# Processing-Section.net
KiCad netlist of a schematic drawn in Altium Designer
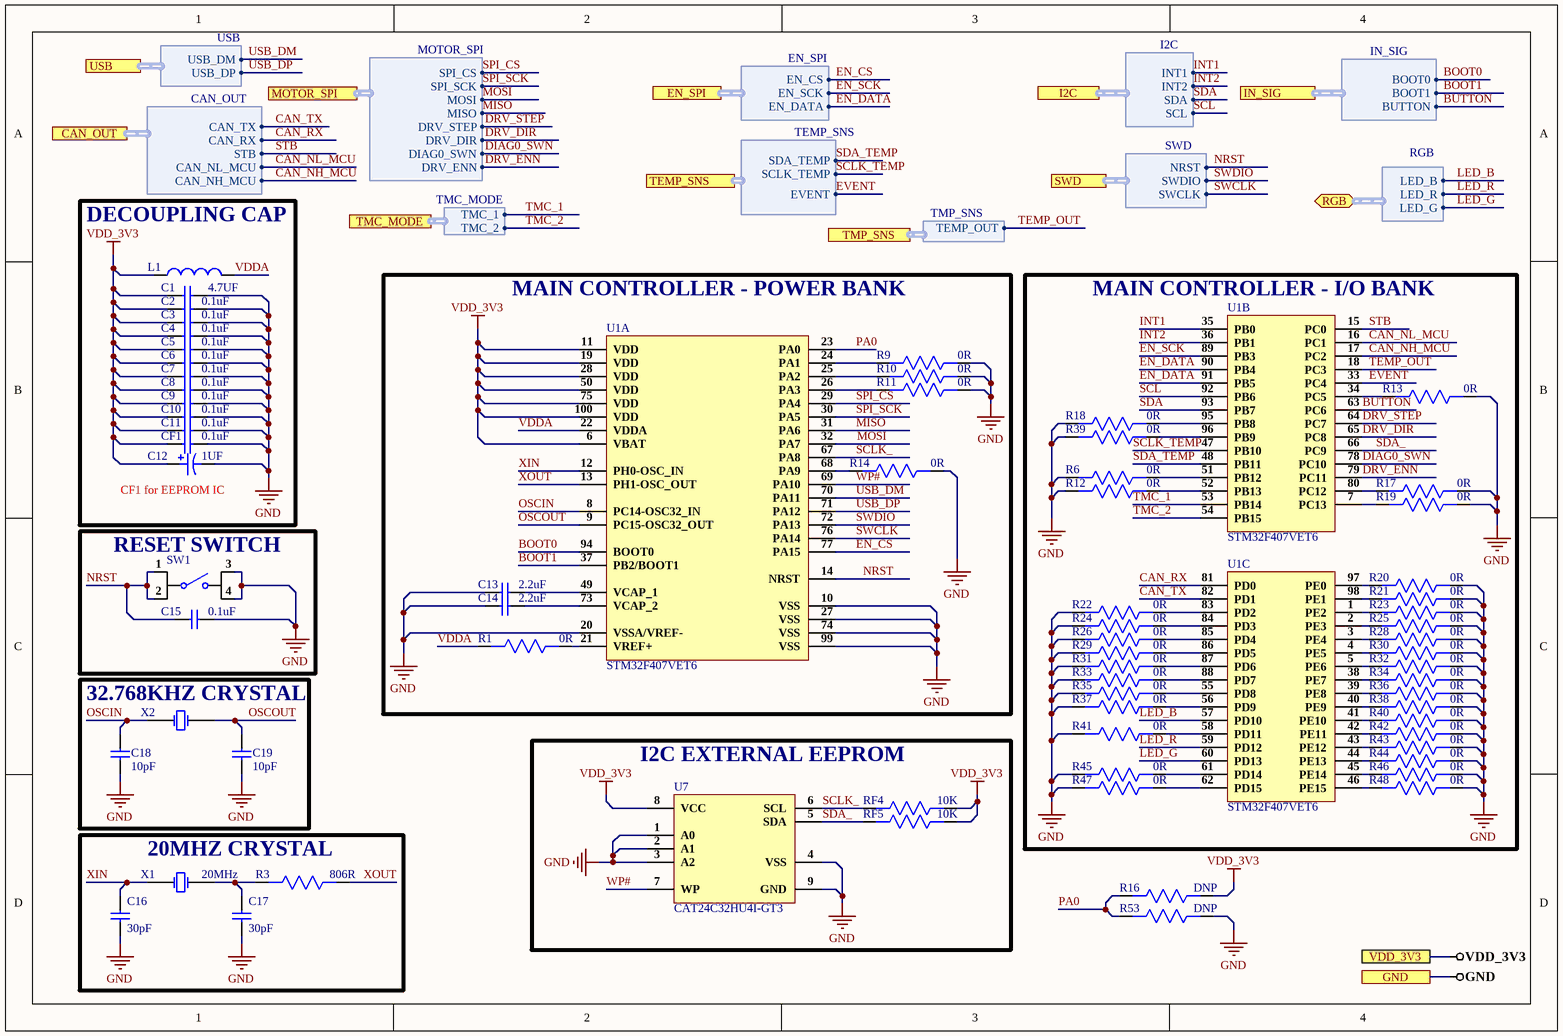
[diagram p0: Processing-Section.SchDoc]

(export (version "E")
  (design (tool "Eeschema 10.0.6"))
  (components
    (comp (ref "C1")
      (value "4.7UF")
      (footprint "Cap0603")
      (description "CAP CER 4.7UF 25V X5R 0603")
      (fields
        (field (name "MANUFACTURER") "Samsung")
        (field (name "MANUFACTURER PART NUMBER") "CL10A475KA8NQNC")
      )
      (libsource (lib "Cole_Benson") (part "CL10A475KA8NQNC"))
    )
    (comp (ref "C2")
      (value "0.1uF")
      (footprint "Cap0603")
      (description "Cap Ceramic 0.1uF 50VDC X7R 10% SMD 0603 Paper T/R")
      (fields
        (field (name "MANUFACTURER") "Samsung")
        (field (name "MANUFACTURER PART NUMBER") "CL10B104KB8NNNC")
      )
      (libsource (lib "Cole_Benson") (part "CL10B104KB8NNNC"))
    )
    (comp (ref "C3")
      (value "0.1uF")
      (footprint "Cap0603")
      (description "Cap Ceramic 0.1uF 50VDC X7R 10% SMD 0603 Paper T/R")
      (fields
        (field (name "MANUFACTURER") "Samsung")
        (field (name "MANUFACTURER PART NUMBER") "CL10B104KB8NNNC")
      )
      (libsource (lib "Cole_Benson") (part "CL10B104KB8NNNC"))
    )
    (comp (ref "C4")
      (value "0.1uF")
      (footprint "Cap0603")
      (description "Cap Ceramic 0.1uF 50VDC X7R 10% SMD 0603 Paper T/R")
      (fields
        (field (name "MANUFACTURER") "Samsung")
        (field (name "MANUFACTURER PART NUMBER") "CL10B104KB8NNNC")
      )
      (libsource (lib "Cole_Benson") (part "CL10B104KB8NNNC"))
    )
    (comp (ref "C5")
      (value "0.1uF")
      (footprint "Cap0603")
      (description "Cap Ceramic 0.1uF 50VDC X7R 10% SMD 0603 Paper T/R")
      (fields
        (field (name "MANUFACTURER") "Samsung")
        (field (name "MANUFACTURER PART NUMBER") "CL10B104KB8NNNC")
      )
      (libsource (lib "Cole_Benson") (part "CL10B104KB8NNNC"))
    )
    (comp (ref "C6")
      (value "0.1uF")
      (footprint "Cap0603")
      (description "Cap Ceramic 0.1uF 50VDC X7R 10% SMD 0603 Paper T/R")
      (fields
        (field (name "MANUFACTURER") "Samsung")
        (field (name "MANUFACTURER PART NUMBER") "CL10B104KB8NNNC")
      )
      (libsource (lib "Cole_Benson") (part "CL10B104KB8NNNC"))
    )
    (comp (ref "C7")
      (value "0.1uF")
      (footprint "Cap0603")
      (description "Cap Ceramic 0.1uF 50VDC X7R 10% SMD 0603 Paper T/R")
      (fields
        (field (name "MANUFACTURER") "Samsung")
        (field (name "MANUFACTURER PART NUMBER") "CL10B104KB8NNNC")
      )
      (libsource (lib "Cole_Benson") (part "CL10B104KB8NNNC"))
    )
    (comp (ref "C8")
      (value "0.1uF")
      (footprint "Cap0603")
      (description "Cap Ceramic 0.1uF 50VDC X7R 10% SMD 0603 Paper T/R")
      (fields
        (field (name "MANUFACTURER") "Samsung")
        (field (name "MANUFACTURER PART NUMBER") "CL10B104KB8NNNC")
      )
      (libsource (lib "Cole_Benson") (part "CL10B104KB8NNNC"))
    )
    (comp (ref "C9")
      (value "0.1uF")
      (footprint "Cap0603")
      (description "Cap Ceramic 0.1uF 50VDC X7R 10% SMD 0603 Paper T/R")
      (fields
        (field (name "MANUFACTURER") "Samsung")
        (field (name "MANUFACTURER PART NUMBER") "CL10B104KB8NNNC")
      )
      (libsource (lib "Cole_Benson") (part "CL10B104KB8NNNC"))
    )
    (comp (ref "C10")
      (value "0.1uF")
      (footprint "Cap0603")
      (description "Cap Ceramic 0.1uF 50VDC X7R 10% SMD 0603 Paper T/R")
      (fields
        (field (name "MANUFACTURER") "Samsung")
        (field (name "MANUFACTURER PART NUMBER") "CL10B104KB8NNNC")
      )
      (libsource (lib "Cole_Benson") (part "CL10B104KB8NNNC"))
    )
    (comp (ref "C11")
      (value "0.1uF")
      (footprint "Cap0603")
      (description "Cap Ceramic 0.1uF 50VDC X7R 10% SMD 0603 Paper T/R")
      (fields
        (field (name "MANUFACTURER") "Samsung")
        (field (name "MANUFACTURER PART NUMBER") "CL10B104KB8NNNC")
      )
      (libsource (lib "Cole_Benson") (part "CL10B104KB8NNNC"))
    )
    (comp (ref "C12")
      (value "1UF")
      (footprint "CAP-CASE A")
      (description "CAP TANT 1UF 10% 16V 1206")
      (fields
        (field (name "MANUFACTURER") "Kyocera AVX")
        (field (name "MANUFACTURER PART NUMBER") "TAJA105K016RNJ")
      )
      (libsource (lib "Cole_Benson") (part "TAJA105K016RNJ"))
    )
    (comp (ref "C13")
      (value "2.2uF")
      (footprint "Cap 0603")
      (description "CAP, 2.2µF, 35V, 10%, X5R, 0603")
      (fields
        (field (name "MANUFACTURER") "Murata")
        (field (name "MANUFACTURER PART NUMBER") "GRM188R6YA225KA12D")
      )
      (libsource (lib "Cole_Benson") (part "GRM188R6YA225KA12D"))
    )
    (comp (ref "C14")
      (value "2.2uF")
      (footprint "Cap 0603")
      (description "CAP, 2.2µF, 35V, 10%, X5R, 0603")
      (fields
        (field (name "MANUFACTURER") "Murata")
        (field (name "MANUFACTURER PART NUMBER") "GRM188R6YA225KA12D")
      )
      (libsource (lib "Cole_Benson") (part "GRM188R6YA225KA12D"))
    )
    (comp (ref "C15")
      (value "0.1uF")
      (footprint "Cap0603")
      (description "Cap Ceramic 0.1uF 50VDC X7R 10% SMD 0603 Paper T/R")
      (fields
        (field (name "MANUFACTURER") "Samsung")
        (field (name "MANUFACTURER PART NUMBER") "CL10B104KB8NNNC")
      )
      (libsource (lib "Cole_Benson") (part "CL10B104KB8NNNC"))
    )
    (comp (ref "C16")
      (value "30pF")
      (footprint "Cap 0603")
      (description "CAP 30pF NP0 0603 50 V ±5 % SMD")
      (fields
        (field (name "MANUFACTURER") "Yageo")
        (field (name "MANUFACTURER PART NUMBER") "CC0603JRNPO9BN300")
      )
      (libsource (lib "Cole_Benson") (part "CC0603JRNPO9BN300"))
    )
    (comp (ref "C17")
      (value "30pF")
      (footprint "Cap 0603")
      (description "CAP 30pF NP0 0603 50 V ±5 % SMD")
      (fields
        (field (name "MANUFACTURER") "Yageo")
        (field (name "MANUFACTURER PART NUMBER") "CC0603JRNPO9BN300")
      )
      (libsource (lib "Cole_Benson") (part "CC0603JRNPO9BN300"))
    )
    (comp (ref "C18")
      (value "10pF")
      (footprint "CAP 0201")
      (description "CAP CER 10PF 25V C0G 0201")
      (fields
        (field (name "MANUFACTURER") "TDK")
        (field (name "MANUFACTURER PART NUMBER") "CGA1A2C0G1E100D030BA")
      )
      (libsource (lib "Cole_Benson") (part "CGA1A2C0G1E100D030BA"))
    )
    (comp (ref "C19")
      (value "10pF")
      (footprint "CAP 0201")
      (description "CAP CER 10PF 25V C0G 0201")
      (fields
        (field (name "MANUFACTURER") "TDK")
        (field (name "MANUFACTURER PART NUMBER") "CGA1A2C0G1E100D030BA")
      )
      (libsource (lib "Cole_Benson") (part "CGA1A2C0G1E100D030BA"))
    )
    (comp (ref "CF1")
      (value "0.1uF")
      (footprint "Cap 0603")
      (description "Cap Ceramic 0.1uF 50VDC X7R 10% SMD 0603 Paper T/R")
      (fields
        (field (name "MANUFACTURER") "Samsung")
        (field (name "MANUFACTURER PART NUMBER") "CL10B104KB8NNNC")
      )
      (libsource (lib "Cole_Benson") (part "CL10B104KB8NNNC"))
    )
    (comp (ref "L1")
      (value "FBMH1608HL121-TV")
      (footprint "IND 0603")
      (description "Ferrite Beads 120Ohm 25% 100MHz 1.2A 0.13Ohm DCR 0603 Automotive T/R")
      (fields (field (name "MANUFACTURER") "Taiyo Yuden") (field (name "TOLERANCE") "25%"))
      (libsource (lib "Cole_Benson") (part "FBMH1608HL121-TV"))
    )
    (comp (ref "R1")
      (value "0R")
      (footprint "Res-0201")
      (description "RES SMD 0 OHM JUMPER 1/20W 0201")
      (fields
        (field (name "MANUFACTURER") "Yageo")
        (field (name "MANUFACTURER PART NUMBER") "RC0201JR-070RL")
      )
      (libsource (lib "Cole_Benson") (part "RC0201JR-070RL"))
    )
    (comp (ref "R3")
      (value "806R")
      (footprint "Res-0201")
      (description "Res Thick Film 0201 806 Ohm 1% 1/20W ±200ppm/°C Molded SMD SMD Paper T/R")
      (fields
        (field (name "MANUFACTURER") "Stackpole Electronics")
        (field (name "MANUFACTURER PART NUMBER") "RMCF0201FT806R")
      )
      (libsource (lib "Cole_Benson") (part "RMCF0201FT806R"))
    )
    (comp (ref "R6")
      (value "0R")
      (footprint "Res-0201")
      (description "RES SMD 0 OHM JUMPER 1/20W 0201")
      (fields
        (field (name "MANUFACTURER") "Yageo")
        (field (name "MANUFACTURER PART NUMBER") "RC0201JR-070RL")
      )
      (libsource (lib "Cole_Benson") (part "RC0201JR-070RL"))
    )
    (comp (ref "R9")
      (value "0R")
      (footprint "Res-0201")
      (description "RES SMD 0 OHM JUMPER 1/20W 0201")
      (fields
        (field (name "MANUFACTURER") "Yageo")
        (field (name "MANUFACTURER PART NUMBER") "RC0201JR-070RL")
      )
      (libsource (lib "Cole_Benson") (part "RC0201JR-070RL"))
    )
    (comp (ref "R10")
      (value "0R")
      (footprint "Res-0201")
      (description "RES SMD 0 OHM JUMPER 1/20W 0201")
      (fields
        (field (name "MANUFACTURER") "Yageo")
        (field (name "MANUFACTURER PART NUMBER") "RC0201JR-070RL")
      )
      (libsource (lib "Cole_Benson") (part "RC0201JR-070RL"))
    )
    (comp (ref "R11")
      (value "0R")
      (footprint "Res-0201")
      (description "RES SMD 0 OHM JUMPER 1/20W 0201")
      (fields
        (field (name "MANUFACTURER") "Yageo")
        (field (name "MANUFACTURER PART NUMBER") "RC0201JR-070RL")
      )
      (libsource (lib "Cole_Benson") (part "RC0201JR-070RL"))
    )
    (comp (ref "R12")
      (value "0R")
      (footprint "Res-0201")
      (description "RES SMD 0 OHM JUMPER 1/20W 0201")
      (fields
        (field (name "MANUFACTURER") "Yageo")
        (field (name "MANUFACTURER PART NUMBER") "RC0201JR-070RL")
      )
      (libsource (lib "Cole_Benson") (part "RC0201JR-070RL"))
    )
    (comp (ref "R13")
      (value "0R")
      (footprint "Res-0201")
      (description "RES SMD 0 OHM JUMPER 1/20W 0201")
      (fields
        (field (name "MANUFACTURER") "Yageo")
        (field (name "MANUFACTURER PART NUMBER") "RC0201JR-070RL")
      )
      (libsource (lib "Cole_Benson") (part "RC0201JR-070RL"))
    )
    (comp (ref "R14")
      (value "0R")
      (footprint "Res-0201")
      (description "RES SMD 0 OHM JUMPER 1/20W 0201")
      (fields
        (field (name "MANUFACTURER") "Yageo")
        (field (name "MANUFACTURER PART NUMBER") "RC0201JR-070RL")
      )
      (libsource (lib "Cole_Benson") (part "RC0201JR-070RL"))
    )
    (comp (ref "R16")
      (value "DNP")
      (footprint "Res0603")
      (description "RES SMD 10K Ohm 1% 1/10W 0603")
      (fields
        (field (name "MANUFACTURER") "Yageo")
        (field (name "MANUFACTURER PART NUMBER") "RC0603FR-0710KL")
      )
      (libsource (lib "Cole_Benson") (part "RC0603FR-0710KL"))
    )
    (comp (ref "R17")
      (value "0R")
      (footprint "Res-0201")
      (description "RES SMD 0 OHM JUMPER 1/20W 0201")
      (fields
        (field (name "MANUFACTURER") "Yageo")
        (field (name "MANUFACTURER PART NUMBER") "RC0201JR-070RL")
      )
      (libsource (lib "Cole_Benson") (part "RC0201JR-070RL"))
    )
    (comp (ref "R18")
      (value "0R")
      (footprint "Res-0201")
      (description "RES SMD 0 OHM JUMPER 1/20W 0201")
      (fields
        (field (name "MANUFACTURER") "Yageo")
        (field (name "MANUFACTURER PART NUMBER") "RC0201JR-070RL")
      )
      (libsource (lib "Cole_Benson") (part "RC0201JR-070RL"))
    )
    (comp (ref "R19")
      (value "0R")
      (footprint "Res-0201")
      (description "RES SMD 0 OHM JUMPER 1/20W 0201")
      (fields
        (field (name "MANUFACTURER") "Yageo")
        (field (name "MANUFACTURER PART NUMBER") "RC0201JR-070RL")
      )
      (libsource (lib "Cole_Benson") (part "RC0201JR-070RL"))
    )
    (comp (ref "R20")
      (value "0R")
      (footprint "Res-0201")
      (description "RES SMD 0 OHM JUMPER 1/20W 0201")
      (fields
        (field (name "MANUFACTURER") "Yageo")
        (field (name "MANUFACTURER PART NUMBER") "RC0201JR-070RL")
      )
      (libsource (lib "Cole_Benson") (part "RC0201JR-070RL"))
    )
    (comp (ref "R21")
      (value "0R")
      (footprint "Res-0201")
      (description "RES SMD 0 OHM JUMPER 1/20W 0201")
      (fields
        (field (name "MANUFACTURER") "Yageo")
        (field (name "MANUFACTURER PART NUMBER") "RC0201JR-070RL")
      )
      (libsource (lib "Cole_Benson") (part "RC0201JR-070RL"))
    )
    (comp (ref "R22")
      (value "0R")
      (footprint "Res-0201")
      (description "RES SMD 0 OHM JUMPER 1/20W 0201")
      (fields
        (field (name "MANUFACTURER") "Yageo")
        (field (name "MANUFACTURER PART NUMBER") "RC0201JR-070RL")
      )
      (libsource (lib "Cole_Benson") (part "RC0201JR-070RL"))
    )
    (comp (ref "R23")
      (value "0R")
      (footprint "Res-0201")
      (description "RES SMD 0 OHM JUMPER 1/20W 0201")
      (fields
        (field (name "MANUFACTURER") "Yageo")
        (field (name "MANUFACTURER PART NUMBER") "RC0201JR-070RL")
      )
      (libsource (lib "Cole_Benson") (part "RC0201JR-070RL"))
    )
    (comp (ref "R24")
      (value "0R")
      (footprint "Res-0201")
      (description "RES SMD 0 OHM JUMPER 1/20W 0201")
      (fields
        (field (name "MANUFACTURER") "Yageo")
        (field (name "MANUFACTURER PART NUMBER") "RC0201JR-070RL")
      )
      (libsource (lib "Cole_Benson") (part "RC0201JR-070RL"))
    )
    (comp (ref "R25")
      (value "0R")
      (footprint "Res-0201")
      (description "RES SMD 0 OHM JUMPER 1/20W 0201")
      (fields
        (field (name "MANUFACTURER") "Yageo")
        (field (name "MANUFACTURER PART NUMBER") "RC0201JR-070RL")
      )
      (libsource (lib "Cole_Benson") (part "RC0201JR-070RL"))
    )
    (comp (ref "R26")
      (value "0R")
      (footprint "Res-0201")
      (description "RES SMD 0 OHM JUMPER 1/20W 0201")
      (fields
        (field (name "MANUFACTURER") "Yageo")
        (field (name "MANUFACTURER PART NUMBER") "RC0201JR-070RL")
      )
      (libsource (lib "Cole_Benson") (part "RC0201JR-070RL"))
    )
    (comp (ref "R28")
      (value "0R")
      (footprint "Res-0201")
      (description "RES SMD 0 OHM JUMPER 1/20W 0201")
      (fields
        (field (name "MANUFACTURER") "Yageo")
        (field (name "MANUFACTURER PART NUMBER") "RC0201JR-070RL")
      )
      (libsource (lib "Cole_Benson") (part "RC0201JR-070RL"))
    )
    (comp (ref "R29")
      (value "0R")
      (footprint "Res-0201")
      (description "RES SMD 0 OHM JUMPER 1/20W 0201")
      (fields
        (field (name "MANUFACTURER") "Yageo")
        (field (name "MANUFACTURER PART NUMBER") "RC0201JR-070RL")
      )
      (libsource (lib "Cole_Benson") (part "RC0201JR-070RL"))
    )
    (comp (ref "R30")
      (value "0R")
      (footprint "Res-0201")
      (description "RES SMD 0 OHM JUMPER 1/20W 0201")
      (fields
        (field (name "MANUFACTURER") "Yageo")
        (field (name "MANUFACTURER PART NUMBER") "RC0201JR-070RL")
      )
      (libsource (lib "Cole_Benson") (part "RC0201JR-070RL"))
    )
    (comp (ref "R31")
      (value "0R")
      (footprint "Res-0201")
      (description "RES SMD 0 OHM JUMPER 1/20W 0201")
      (fields
        (field (name "MANUFACTURER") "Yageo")
        (field (name "MANUFACTURER PART NUMBER") "RC0201JR-070RL")
      )
      (libsource (lib "Cole_Benson") (part "RC0201JR-070RL"))
    )
    (comp (ref "R32")
      (value "0R")
      (footprint "Res-0201")
      (description "RES SMD 0 OHM JUMPER 1/20W 0201")
      (fields
        (field (name "MANUFACTURER") "Yageo")
        (field (name "MANUFACTURER PART NUMBER") "RC0201JR-070RL")
      )
      (libsource (lib "Cole_Benson") (part "RC0201JR-070RL"))
    )
    (comp (ref "R33")
      (value "0R")
      (footprint "Res-0201")
      (description "RES SMD 0 OHM JUMPER 1/20W 0201")
      (fields
        (field (name "MANUFACTURER") "Yageo")
        (field (name "MANUFACTURER PART NUMBER") "RC0201JR-070RL")
      )
      (libsource (lib "Cole_Benson") (part "RC0201JR-070RL"))
    )
    (comp (ref "R34")
      (value "0R")
      (footprint "Res-0201")
      (description "RES SMD 0 OHM JUMPER 1/20W 0201")
      (fields
        (field (name "MANUFACTURER") "Yageo")
        (field (name "MANUFACTURER PART NUMBER") "RC0201JR-070RL")
      )
      (libsource (lib "Cole_Benson") (part "RC0201JR-070RL"))
    )
    (comp (ref "R35")
      (value "0R")
      (footprint "Res-0201")
      (description "RES SMD 0 OHM JUMPER 1/20W 0201")
      (fields
        (field (name "MANUFACTURER") "Yageo")
        (field (name "MANUFACTURER PART NUMBER") "RC0201JR-070RL")
      )
      (libsource (lib "Cole_Benson") (part "RC0201JR-070RL"))
    )
    (comp (ref "R36")
      (value "0R")
      (footprint "Res-0201")
      (description "RES SMD 0 OHM JUMPER 1/20W 0201")
      (fields
        (field (name "MANUFACTURER") "Yageo")
        (field (name "MANUFACTURER PART NUMBER") "RC0201JR-070RL")
      )
      (libsource (lib "Cole_Benson") (part "RC0201JR-070RL"))
    )
    (comp (ref "R37")
      (value "0R")
      (footprint "Res-0201")
      (description "RES SMD 0 OHM JUMPER 1/20W 0201")
      (fields
        (field (name "MANUFACTURER") "Yageo")
        (field (name "MANUFACTURER PART NUMBER") "RC0201JR-070RL")
      )
      (libsource (lib "Cole_Benson") (part "RC0201JR-070RL"))
    )
    (comp (ref "R38")
      (value "0R")
      (footprint "Res-0201")
      (description "RES SMD 0 OHM JUMPER 1/20W 0201")
      (fields
        (field (name "MANUFACTURER") "Yageo")
        (field (name "MANUFACTURER PART NUMBER") "RC0201JR-070RL")
      )
      (libsource (lib "Cole_Benson") (part "RC0201JR-070RL"))
    )
    (comp (ref "R39")
      (value "0R")
      (footprint "Res-0201")
      (description "RES SMD 0 OHM JUMPER 1/20W 0201")
      (fields
        (field (name "MANUFACTURER") "Yageo")
        (field (name "MANUFACTURER PART NUMBER") "RC0201JR-070RL")
      )
      (libsource (lib "Cole_Benson") (part "RC0201JR-070RL"))
    )
    (comp (ref "R40")
      (value "0R")
      (footprint "Res-0201")
      (description "RES SMD 0 OHM JUMPER 1/20W 0201")
      (fields
        (field (name "MANUFACTURER") "Yageo")
        (field (name "MANUFACTURER PART NUMBER") "RC0201JR-070RL")
      )
      (libsource (lib "Cole_Benson") (part "RC0201JR-070RL"))
    )
    (comp (ref "R41")
      (value "0R")
      (footprint "Res-0201")
      (description "RES SMD 0 OHM JUMPER 1/20W 0201")
      (fields
        (field (name "MANUFACTURER") "Yageo")
        (field (name "MANUFACTURER PART NUMBER") "RC0201JR-070RL")
      )
      (libsource (lib "Cole_Benson") (part "RC0201JR-070RL"))
    )
    (comp (ref "R42")
      (value "0R")
      (footprint "Res-0201")
      (description "RES SMD 0 OHM JUMPER 1/20W 0201")
      (fields
        (field (name "MANUFACTURER") "Yageo")
        (field (name "MANUFACTURER PART NUMBER") "RC0201JR-070RL")
      )
      (libsource (lib "Cole_Benson") (part "RC0201JR-070RL"))
    )
    (comp (ref "R43")
      (value "0R")
      (footprint "Res-0201")
      (description "RES SMD 0 OHM JUMPER 1/20W 0201")
      (fields
        (field (name "MANUFACTURER") "Yageo")
        (field (name "MANUFACTURER PART NUMBER") "RC0201JR-070RL")
      )
      (libsource (lib "Cole_Benson") (part "RC0201JR-070RL"))
    )
    (comp (ref "R44")
      (value "0R")
      (footprint "Res-0201")
      (description "RES SMD 0 OHM JUMPER 1/20W 0201")
      (fields
        (field (name "MANUFACTURER") "Yageo")
        (field (name "MANUFACTURER PART NUMBER") "RC0201JR-070RL")
      )
      (libsource (lib "Cole_Benson") (part "RC0201JR-070RL"))
    )
    (comp (ref "R45")
      (value "0R")
      (footprint "Res-0201")
      (description "RES SMD 0 OHM JUMPER 1/20W 0201")
      (fields
        (field (name "MANUFACTURER") "Yageo")
        (field (name "MANUFACTURER PART NUMBER") "RC0201JR-070RL")
      )
      (libsource (lib "Cole_Benson") (part "RC0201JR-070RL"))
    )
    (comp (ref "R46")
      (value "0R")
      (footprint "Res-0201")
      (description "RES SMD 0 OHM JUMPER 1/20W 0201")
      (fields
        (field (name "MANUFACTURER") "Yageo")
        (field (name "MANUFACTURER PART NUMBER") "RC0201JR-070RL")
      )
      (libsource (lib "Cole_Benson") (part "RC0201JR-070RL"))
    )
    (comp (ref "R47")
      (value "0R")
      (footprint "Res-0201")
      (description "RES SMD 0 OHM JUMPER 1/20W 0201")
      (fields
        (field (name "MANUFACTURER") "Yageo")
        (field (name "MANUFACTURER PART NUMBER") "RC0201JR-070RL")
      )
      (libsource (lib "Cole_Benson") (part "RC0201JR-070RL"))
    )
    (comp (ref "R48")
      (value "0R")
      (footprint "Res-0201")
      (description "RES SMD 0 OHM JUMPER 1/20W 0201")
      (fields
        (field (name "MANUFACTURER") "Yageo")
        (field (name "MANUFACTURER PART NUMBER") "RC0201JR-070RL")
      )
      (libsource (lib "Cole_Benson") (part "RC0201JR-070RL"))
    )
    (comp (ref "R53")
      (value "DNP")
      (footprint "Res0603")
      (description "RES SMD 10K Ohm 1% 1/10W 0603")
      (fields
        (field (name "MANUFACTURER") "Yageo")
        (field (name "MANUFACTURER PART NUMBER") "RC0603FR-0710KL")
      )
      (libsource (lib "Cole_Benson") (part "RC0603FR-0710KL"))
    )
    (comp (ref "RF4")
      (value "10K")
      (footprint "Res0603")
      (description "RES SMD 10K Ohm 1% 1/10W 0603")
      (fields
        (field (name "MANUFACTURER") "Yageo")
        (field (name "MANUFACTURER PART NUMBER") "RC0603FR-0710KL")
      )
      (libsource (lib "Cole_Benson") (part "RC0603FR-0710KL"))
    )
    (comp (ref "RF5")
      (value "10K")
      (footprint "Res0603")
      (description "RES SMD 10K Ohm 1% 1/10W 0603")
      (fields
        (field (name "MANUFACTURER") "Yageo")
        (field (name "MANUFACTURER PART NUMBER") "RC0603FR-0710KL")
      )
      (libsource (lib "Cole_Benson") (part "RC0603FR-0710KL"))
    )
    (comp (ref "SW1")
      (value "GT-TC025D-H0065-L1")
      (footprint "GT-TC025D-H0065-L1")
      (fields (field (name "MANUFACTURER") "G-Switch"))
      (libsource (lib "Cole_Benson") (part "GT-TC025D-H0065-L1"))
    )
    (comp (ref "U1")
      (value "STM32F407VET6")
      (footprint "LQFP-100")
      (description "IC MCU 32BIT 512KB FLASH 100LQFP")
      (fields (field (name "MANUFACTURER") "STMicroelectronics"))
      (libsource (lib "Cole_Benson") (part "STM32F407VET6"))
    )
    (comp (ref "U7")
      (value "CAT24C32HU4I-GT3")
      (footprint "8-UDFN-EP (2x3)")
      (description "IC EEPROM 32KBIT I2C 1MHZ 8UDFN")
      (fields (field (name "MANUFACTURER") "ON Semiconductor"))
      (libsource (lib "Cole_Benson") (part "CAT24C32HU4I-GT3"))
    )
    (comp (ref "X1")
      (value "20MHz")
      (footprint "HCM4920000000ABJT")
      (description "CRYSTAL 20.0000MHZ 18PF SMD")
      (fields
        (field (name "MANUFACTURER") "CITIZEN")
        (field (name "MANUFACTURER PART NUMBER") "HCM4920000000ABJT")
      )
      (libsource (lib "Cole_Benson") (part "HCM4920000000ABJT"))
    )
    (comp (ref "X2")
      (value "ECS-.327-7-34B-C-TR")
      (footprint "ECS-.327-7-34B-C-TR")
      (description "Crystals 32.768KHz 7pF")
      (fields (field (name "MANUFACTURER") "ECS International"))
      (libsource (lib "Cole_Benson") (part "ECS-.327-7-34B-C-TR"))
    )
  )
  (nets
    (net (code "12") (name "/BOOT0") (class "Default")
      (node (ref "U1") (pin "94") (pinfunction "BOOT0_94") (pintype "passive"))
    )
    (net (code "13") (name "/BOOT1") (class "Default")
      (node (ref "U1") (pin "37") (pinfunction "PB2/BOOT1_37") (pintype "passive"))
    )
    (net (code "14") (name "/BUTTON") (class "Default")
      (node (ref "U1") (pin "63") (pinfunction "PC6_63") (pintype "passive"))
    )
    (net (code "15") (name "/CAN_NH_MCU") (class "Default")
      (node (ref "U1") (pin "17") (pinfunction "PC2_17") (pintype "passive"))
    )
    (net (code "16") (name "/CAN_NL_MCU") (class "Default")
      (node (ref "U1") (pin "16") (pinfunction "PC1_16") (pintype "passive"))
    )
    (net (code "17") (name "/CAN_RX") (class "Default")
      (node (ref "U1") (pin "81") (pinfunction "PD0_81") (pintype "passive"))
    )
    (net (code "18") (name "/CAN_TX") (class "Default")
      (node (ref "U1") (pin "82") (pinfunction "PD1_82") (pintype "passive"))
    )
    (net (code "19") (name "/DIAG0_SWN") (class "Default")
      (node (ref "U1") (pin "78") (pinfunction "PC10_78") (pintype "passive"))
    )
    (net (code "20") (name "/DRV_DIR") (class "Default")
      (node (ref "U1") (pin "65") (pinfunction "PC8_65") (pintype "passive"))
    )
    (net (code "21") (name "/DRV_ENN") (class "Default")
      (node (ref "U1") (pin "79") (pinfunction "PC11_79") (pintype "passive"))
    )
    (net (code "22") (name "/DRV_STEP") (class "Default")
      (node (ref "U1") (pin "64") (pinfunction "PC7_64") (pintype "passive"))
    )
    (net (code "23") (name "/EN_CS") (class "Default")
      (node (ref "U1") (pin "77") (pinfunction "PA15_77") (pintype "passive"))
    )
    (net (code "24") (name "/EN_DATA") (class "Default")
      (node (ref "U1") (pin "90") (pinfunction "PB4_90") (pintype "passive"))
      (node (ref "U1") (pin "91") (pinfunction "PB5_91") (pintype "passive"))
    )
    (net (code "25") (name "/EN_SCK") (class "Default")
      (node (ref "U1") (pin "89") (pinfunction "PB3_89") (pintype "passive"))
    )
    (net (code "26") (name "/EVENT") (class "Default")
      (node (ref "U1") (pin "33") (pinfunction "PC4_33") (pintype "passive"))
    )
    (net (code "27") (name "/INT1") (class "Default")
      (node (ref "U1") (pin "35") (pinfunction "PB0_35") (pintype "passive"))
    )
    (net (code "28") (name "/INT2") (class "Default")
      (node (ref "U1") (pin "36") (pinfunction "PB1_36") (pintype "passive"))
    )
    (net (code "29") (name "/LED_B") (class "Default")
      (node (ref "U1") (pin "57") (pinfunction "PD10_57") (pintype "passive"))
    )
    (net (code "30") (name "/LED_G") (class "Default")
      (node (ref "U1") (pin "60") (pinfunction "PD13_60") (pintype "passive"))
    )
    (net (code "31") (name "/LED_R") (class "Default")
      (node (ref "U1") (pin "59") (pinfunction "PD12_59") (pintype "passive"))
    )
    (net (code "32") (name "/MISO") (class "Default")
      (node (ref "U1") (pin "31") (pinfunction "PA6_31") (pintype "passive"))
    )
    (net (code "33") (name "/MOSI") (class "Default")
      (node (ref "U1") (pin "32") (pinfunction "PA7_32") (pintype "passive"))
    )
    (net (code "34") (name "/NRST") (class "Default")
      (node (ref "C15") (pin "1") (pinfunction "1_1") (pintype "passive"))
      (node (ref "SW1") (pin "1") (pinfunction "1_1") (pintype "passive"))
      (node (ref "SW1") (pin "2") (pinfunction "2_2") (pintype "passive"))
      (node (ref "U1") (pin "14") (pinfunction "NRST_14") (pintype "passive"))
    )
    (net (code "35") (name "/OSCIN") (class "Default")
      (node (ref "C18") (pin "2") (pinfunction "2_2") (pintype "passive"))
      (node (ref "U1") (pin "8") (pinfunction "PC14-OSC32_IN_8") (pintype "passive"))
      (node (ref "X2") (pin "1") (pinfunction "OSC1_1") (pintype "passive"))
    )
    (net (code "36") (name "/OSCOUT") (class "Default")
      (node (ref "C19") (pin "2") (pinfunction "2_2") (pintype "passive"))
      (node (ref "U1") (pin "9") (pinfunction "PC15-OSC32_OUT_9") (pintype "passive"))
      (node (ref "X2") (pin "2") (pinfunction "OSC2_2") (pintype "passive"))
    )
    (net (code "37") (name "/PA0") (class "Default")
      (node (ref "R16") (pin "2") (pintype "passive"))
      (node (ref "R53") (pin "2") (pintype "passive"))
      (node (ref "U1") (pin "23") (pinfunction "PA0_23") (pintype "passive"))
    )
    (net (code "38") (name "/SCL") (class "Default")
      (node (ref "U1") (pin "92") (pinfunction "PB6_92") (pintype "passive"))
    )
    (net (code "39") (name "/SCLK_") (class "Default")
      (node (ref "RF4") (pin "2") (pintype "passive"))
      (node (ref "U1") (pin "67") (pinfunction "PA8_67") (pintype "passive"))
      (node (ref "U7") (pin "6") (pinfunction "SCL_6") (pintype "passive"))
    )
    (net (code "40") (name "/SCLK_TEMP") (class "Default")
      (node (ref "U1") (pin "47") (pinfunction "PB10_47") (pintype "passive"))
    )
    (net (code "41") (name "/SDA") (class "Default")
      (node (ref "U1") (pin "93") (pinfunction "PB7_93") (pintype "passive"))
    )
    (net (code "42") (name "/SDA_") (class "Default")
      (node (ref "RF5") (pin "2") (pintype "passive"))
      (node (ref "U1") (pin "66") (pinfunction "PC9_66") (pintype "passive"))
      (node (ref "U7") (pin "5") (pinfunction "SDA_5") (pintype "passive"))
    )
    (net (code "43") (name "/SDA_TEMP") (class "Default")
      (node (ref "U1") (pin "48") (pinfunction "PB11_48") (pintype "passive"))
    )
    (net (code "44") (name "/SPI_CS") (class "Default")
      (node (ref "U1") (pin "29") (pinfunction "PA4_29") (pintype "passive"))
    )
    (net (code "45") (name "/SPI_SCK") (class "Default")
      (node (ref "U1") (pin "30") (pinfunction "PA5_30") (pintype "passive"))
    )
    (net (code "46") (name "/STB") (class "Default")
      (node (ref "U1") (pin "15") (pinfunction "PC0_15") (pintype "passive"))
    )
    (net (code "47") (name "/SWCLK") (class "Default")
      (node (ref "U1") (pin "76") (pinfunction "PA14_76") (pintype "passive"))
    )
    (net (code "48") (name "/SWDIO") (class "Default")
      (node (ref "U1") (pin "72") (pinfunction "PA13_72") (pintype "passive"))
    )
    (net (code "49") (name "/TEMP_OUT") (class "Default")
      (node (ref "U1") (pin "18") (pinfunction "PC3_18") (pintype "passive"))
    )
    (net (code "50") (name "/TMC_1") (class "Default")
      (node (ref "U1") (pin "53") (pinfunction "PB14_53") (pintype "passive"))
    )
    (net (code "51") (name "/TMC_2") (class "Default")
      (node (ref "U1") (pin "54") (pinfunction "PB15_54") (pintype "passive"))
    )
    (net (code "52") (name "/USB_DM") (class "Default")
      (node (ref "U1") (pin "70") (pinfunction "PA11_70") (pintype "passive"))
    )
    (net (code "53") (name "/USB_DP") (class "Default")
      (node (ref "U1") (pin "71") (pinfunction "PA12_71") (pintype "passive"))
    )
    (net (code "54") (name "/VDDA") (class "Default")
      (node (ref "L1") (pin "2") (pinfunction "2_2") (pintype "passive"))
      (node (ref "R1") (pin "2") (pintype "passive"))
      (node (ref "U1") (pin "22") (pinfunction "VDDA_22") (pintype "passive"))
    )
    (net (code "55") (name "/WP#") (class "Default")
      (node (ref "U1") (pin "69") (pinfunction "PA10_69") (pintype "passive"))
      (node (ref "U7") (pin "7") (pinfunction "WP_7") (pintype "passive"))
    )
    (net (code "56") (name "/XIN") (class "Default")
      (node (ref "C16") (pin "2") (pinfunction "2_2") (pintype "passive"))
      (node (ref "U1") (pin "12") (pinfunction "PH0-OSC_IN_12") (pintype "passive"))
      (node (ref "X1") (pin "1") (pinfunction "OSC1_1") (pintype "passive"))
    )
    (net (code "57") (name "/XOUT") (class "Default")
      (node (ref "R3") (pin "1") (pintype "passive"))
      (node (ref "U1") (pin "13") (pinfunction "PH1-OSC_OUT_13") (pintype "passive"))
    )
    (net (code "69") (name "GND") (class "Default")
      (node (ref "C1") (pin "2") (pinfunction "2_2") (pintype "passive"))
      (node (ref "C10") (pin "2") (pinfunction "2_2") (pintype "passive"))
      (node (ref "C11") (pin "2") (pinfunction "2_2") (pintype "passive"))
      (node (ref "C12") (pin "2") (pinfunction "2_2") (pintype "passive"))
      (node (ref "C13") (pin "1") (pinfunction "1_1") (pintype "passive"))
      (node (ref "C14") (pin "1") (pinfunction "1_1") (pintype "passive"))
      (node (ref "C15") (pin "2") (pinfunction "2_2") (pintype "passive"))
      (node (ref "C16") (pin "1") (pinfunction "1_1") (pintype "passive"))
      (node (ref "C17") (pin "1") (pinfunction "1_1") (pintype "passive"))
      (node (ref "C18") (pin "1") (pinfunction "1_1") (pintype "passive"))
      (node (ref "C19") (pin "1") (pinfunction "1_1") (pintype "passive"))
      (node (ref "C2") (pin "2") (pinfunction "2_2") (pintype "passive"))
      (node (ref "C3") (pin "2") (pinfunction "2_2") (pintype "passive"))
      (node (ref "C4") (pin "2") (pinfunction "2_2") (pintype "passive"))
      (node (ref "C5") (pin "2") (pinfunction "2_2") (pintype "passive"))
      (node (ref "C6") (pin "2") (pinfunction "2_2") (pintype "passive"))
      (node (ref "C7") (pin "2") (pinfunction "2_2") (pintype "passive"))
      (node (ref "C8") (pin "2") (pinfunction "2_2") (pintype "passive"))
      (node (ref "C9") (pin "2") (pinfunction "2_2") (pintype "passive"))
      (node (ref "CF1") (pin "2") (pinfunction "2_2") (pintype "passive"))
      (node (ref "R10") (pin "1") (pintype "passive"))
      (node (ref "R11") (pin "1") (pintype "passive"))
      (node (ref "R12") (pin "2") (pintype "passive"))
      (node (ref "R13") (pin "1") (pintype "passive"))
      (node (ref "R14") (pin "1") (pintype "passive"))
      (node (ref "R17") (pin "1") (pintype "passive"))
      (node (ref "R18") (pin "2") (pintype "passive"))
      (node (ref "R19") (pin "1") (pintype "passive"))
      (node (ref "R20") (pin "1") (pintype "passive"))
      (node (ref "R21") (pin "1") (pintype "passive"))
      (node (ref "R22") (pin "2") (pintype "passive"))
      (node (ref "R23") (pin "1") (pintype "passive"))
      (node (ref "R24") (pin "2") (pintype "passive"))
      (node (ref "R25") (pin "1") (pintype "passive"))
      (node (ref "R26") (pin "2") (pintype "passive"))
      (node (ref "R28") (pin "1") (pintype "passive"))
      (node (ref "R29") (pin "2") (pintype "passive"))
      (node (ref "R30") (pin "1") (pintype "passive"))
      (node (ref "R31") (pin "2") (pintype "passive"))
      (node (ref "R32") (pin "1") (pintype "passive"))
      (node (ref "R33") (pin "2") (pintype "passive"))
      (node (ref "R34") (pin "1") (pintype "passive"))
      (node (ref "R35") (pin "2") (pintype "passive"))
      (node (ref "R36") (pin "1") (pintype "passive"))
      (node (ref "R37") (pin "2") (pintype "passive"))
      (node (ref "R38") (pin "1") (pintype "passive"))
      (node (ref "R39") (pin "2") (pintype "passive"))
      (node (ref "R40") (pin "1") (pintype "passive"))
      (node (ref "R41") (pin "2") (pintype "passive"))
      (node (ref "R42") (pin "1") (pintype "passive"))
      (node (ref "R43") (pin "1") (pintype "passive"))
      (node (ref "R44") (pin "1") (pintype "passive"))
      (node (ref "R45") (pin "2") (pintype "passive"))
      (node (ref "R46") (pin "1") (pintype "passive"))
      (node (ref "R47") (pin "2") (pintype "passive"))
      (node (ref "R48") (pin "1") (pintype "passive"))
      (node (ref "R53") (pin "1") (pintype "passive"))
      (node (ref "R6") (pin "2") (pintype "passive"))
      (node (ref "R9") (pin "1") (pintype "passive"))
      (node (ref "SW1") (pin "3") (pinfunction "3_3") (pintype "passive"))
      (node (ref "SW1") (pin "4") (pinfunction "4_4") (pintype "passive"))
      (node (ref "U1") (pin "10") (pinfunction "VSS_10") (pintype "passive"))
      (node (ref "U1") (pin "20") (pinfunction "VSSA/VREF-_20") (pintype "passive"))
      (node (ref "U1") (pin "27") (pinfunction "VSS_27") (pintype "passive"))
      (node (ref "U1") (pin "74") (pinfunction "VSS_74") (pintype "passive"))
      (node (ref "U1") (pin "99") (pinfunction "VSS_99") (pintype "passive"))
      (node (ref "U7") (pin "1") (pinfunction "A0_1") (pintype "passive"))
      (node (ref "U7") (pin "2") (pinfunction "A1_2") (pintype "passive"))
      (node (ref "U7") (pin "3") (pinfunction "A2_3") (pintype "passive"))
      (node (ref "U7") (pin "4") (pinfunction "VSS_4") (pintype "passive"))
      (node (ref "U7") (pin "9") (pinfunction "GND_9") (pintype "passive"))
    )
    (net (code "70") (name "Net-(U1A-PA1)") (class "Default")
      (node (ref "R9") (pin "2") (pintype "passive"))
      (node (ref "U1") (pin "24") (pinfunction "PA1_24") (pintype "passive"))
    )
    (net (code "71") (name "Net-(U1A-PA2)") (class "Default")
      (node (ref "R10") (pin "2") (pintype "passive"))
      (node (ref "U1") (pin "25") (pinfunction "PA2_25") (pintype "passive"))
    )
    (net (code "72") (name "Net-(U1A-PA3)") (class "Default")
      (node (ref "R11") (pin "2") (pintype "passive"))
      (node (ref "U1") (pin "26") (pinfunction "PA3_26") (pintype "passive"))
    )
    (net (code "73") (name "Net-(U1A-PA9)") (class "Default")
      (node (ref "R14") (pin "2") (pintype "passive"))
      (node (ref "U1") (pin "68") (pinfunction "PA9_68") (pintype "passive"))
    )
    (net (code "74") (name "Net-(U1A-VCAP_1)") (class "Default")
      (node (ref "C13") (pin "2") (pinfunction "2_2") (pintype "passive"))
      (node (ref "U1") (pin "49") (pinfunction "VCAP_1_49") (pintype "passive"))
    )
    (net (code "75") (name "Net-(U1A-VCAP_2)") (class "Default")
      (node (ref "C14") (pin "2") (pinfunction "2_2") (pintype "passive"))
      (node (ref "U1") (pin "73") (pinfunction "VCAP_2_73") (pintype "passive"))
    )
    (net (code "76") (name "Net-(U1A-VREF+)") (class "Default")
      (node (ref "R1") (pin "1") (pintype "passive"))
      (node (ref "U1") (pin "21") (pinfunction "VREF+_21") (pintype "passive"))
    )
    (net (code "77") (name "Net-(U1B-PB8)") (class "Default")
      (node (ref "R18") (pin "1") (pintype "passive"))
      (node (ref "U1") (pin "95") (pinfunction "PB8_95") (pintype "passive"))
    )
    (net (code "78") (name "Net-(U1B-PB9)") (class "Default")
      (node (ref "R39") (pin "1") (pintype "passive"))
      (node (ref "U1") (pin "96") (pinfunction "PB9_96") (pintype "passive"))
    )
    (net (code "79") (name "Net-(U1B-PB12)") (class "Default")
      (node (ref "R6") (pin "1") (pintype "passive"))
      (node (ref "U1") (pin "51") (pinfunction "PB12_51") (pintype "passive"))
    )
    (net (code "80") (name "Net-(U1B-PB13)") (class "Default")
      (node (ref "R12") (pin "1") (pintype "passive"))
      (node (ref "U1") (pin "52") (pinfunction "PB13_52") (pintype "passive"))
    )
    (net (code "81") (name "Net-(U1B-PC5)") (class "Default")
      (node (ref "R13") (pin "2") (pintype "passive"))
      (node (ref "U1") (pin "34") (pinfunction "PC5_34") (pintype "passive"))
    )
    (net (code "82") (name "Net-(U1B-PC12)") (class "Default")
      (node (ref "R17") (pin "2") (pintype "passive"))
      (node (ref "U1") (pin "80") (pinfunction "PC12_80") (pintype "passive"))
    )
    (net (code "83") (name "Net-(U1B-PC13)") (class "Default")
      (node (ref "R19") (pin "2") (pintype "passive"))
      (node (ref "U1") (pin "7") (pinfunction "PC13_7") (pintype "passive"))
    )
    (net (code "84") (name "Net-(U1C-PD2)") (class "Default")
      (node (ref "R22") (pin "1") (pintype "passive"))
      (node (ref "U1") (pin "83") (pinfunction "PD2_83") (pintype "passive"))
    )
    (net (code "85") (name "Net-(U1C-PD3)") (class "Default")
      (node (ref "R24") (pin "1") (pintype "passive"))
      (node (ref "U1") (pin "84") (pinfunction "PD3_84") (pintype "passive"))
    )
    (net (code "86") (name "Net-(U1C-PD4)") (class "Default")
      (node (ref "R26") (pin "1") (pintype "passive"))
      (node (ref "U1") (pin "85") (pinfunction "PD4_85") (pintype "passive"))
    )
    (net (code "87") (name "Net-(U1C-PD5)") (class "Default")
      (node (ref "R29") (pin "1") (pintype "passive"))
      (node (ref "U1") (pin "86") (pinfunction "PD5_86") (pintype "passive"))
    )
    (net (code "88") (name "Net-(U1C-PD6)") (class "Default")
      (node (ref "R31") (pin "1") (pintype "passive"))
      (node (ref "U1") (pin "87") (pinfunction "PD6_87") (pintype "passive"))
    )
    (net (code "89") (name "Net-(U1C-PD7)") (class "Default")
      (node (ref "R33") (pin "1") (pintype "passive"))
      (node (ref "U1") (pin "88") (pinfunction "PD7_88") (pintype "passive"))
    )
    (net (code "90") (name "Net-(U1C-PD8)") (class "Default")
      (node (ref "R35") (pin "1") (pintype "passive"))
      (node (ref "U1") (pin "55") (pinfunction "PD8_55") (pintype "passive"))
    )
    (net (code "91") (name "Net-(U1C-PD9)") (class "Default")
      (node (ref "R37") (pin "1") (pintype "passive"))
      (node (ref "U1") (pin "56") (pinfunction "PD9_56") (pintype "passive"))
    )
    (net (code "92") (name "Net-(U1C-PD11)") (class "Default")
      (node (ref "R41") (pin "1") (pintype "passive"))
      (node (ref "U1") (pin "58") (pinfunction "PD11_58") (pintype "passive"))
    )
    (net (code "93") (name "Net-(U1C-PD14)") (class "Default")
      (node (ref "R45") (pin "1") (pintype "passive"))
      (node (ref "U1") (pin "61") (pinfunction "PD14_61") (pintype "passive"))
    )
    (net (code "94") (name "Net-(U1C-PD15)") (class "Default")
      (node (ref "R47") (pin "1") (pintype "passive"))
      (node (ref "U1") (pin "62") (pinfunction "PD15_62") (pintype "passive"))
    )
    (net (code "95") (name "Net-(U1C-PE0)") (class "Default")
      (node (ref "R20") (pin "2") (pintype "passive"))
      (node (ref "U1") (pin "97") (pinfunction "PE0_97") (pintype "passive"))
    )
    (net (code "96") (name "Net-(U1C-PE1)") (class "Default")
      (node (ref "R21") (pin "2") (pintype "passive"))
      (node (ref "U1") (pin "98") (pinfunction "PE1_98") (pintype "passive"))
    )
    (net (code "97") (name "Net-(U1C-PE2)") (class "Default")
      (node (ref "R23") (pin "2") (pintype "passive"))
      (node (ref "U1") (pin "1") (pinfunction "PE2_1") (pintype "passive"))
    )
    (net (code "98") (name "Net-(U1C-PE3)") (class "Default")
      (node (ref "R25") (pin "2") (pintype "passive"))
      (node (ref "U1") (pin "2") (pinfunction "PE3_2") (pintype "passive"))
    )
    (net (code "99") (name "Net-(U1C-PE4)") (class "Default")
      (node (ref "R28") (pin "2") (pintype "passive"))
      (node (ref "U1") (pin "3") (pinfunction "PE4_3") (pintype "passive"))
    )
    (net (code "100") (name "Net-(U1C-PE5)") (class "Default")
      (node (ref "R30") (pin "2") (pintype "passive"))
      (node (ref "U1") (pin "4") (pinfunction "PE5_4") (pintype "passive"))
    )
    (net (code "101") (name "Net-(U1C-PE6)") (class "Default")
      (node (ref "R32") (pin "2") (pintype "passive"))
      (node (ref "U1") (pin "5") (pinfunction "PE6_5") (pintype "passive"))
    )
    (net (code "102") (name "Net-(U1C-PE7)") (class "Default")
      (node (ref "R34") (pin "2") (pintype "passive"))
      (node (ref "U1") (pin "38") (pinfunction "PE7_38") (pintype "passive"))
    )
    (net (code "103") (name "Net-(U1C-PE8)") (class "Default")
      (node (ref "R36") (pin "2") (pintype "passive"))
      (node (ref "U1") (pin "39") (pinfunction "PE8_39") (pintype "passive"))
    )
    (net (code "104") (name "Net-(U1C-PE9)") (class "Default")
      (node (ref "R38") (pin "2") (pintype "passive"))
      (node (ref "U1") (pin "40") (pinfunction "PE9_40") (pintype "passive"))
    )
    (net (code "105") (name "Net-(U1C-PE10)") (class "Default")
      (node (ref "R40") (pin "2") (pintype "passive"))
      (node (ref "U1") (pin "41") (pinfunction "PE10_41") (pintype "passive"))
    )
    (net (code "106") (name "Net-(U1C-PE11)") (class "Default")
      (node (ref "R42") (pin "2") (pintype "passive"))
      (node (ref "U1") (pin "42") (pinfunction "PE11_42") (pintype "passive"))
    )
    (net (code "107") (name "Net-(U1C-PE12)") (class "Default")
      (node (ref "R43") (pin "2") (pintype "passive"))
      (node (ref "U1") (pin "43") (pinfunction "PE12_43") (pintype "passive"))
    )
    (net (code "108") (name "Net-(U1C-PE13)") (class "Default")
      (node (ref "R44") (pin "2") (pintype "passive"))
      (node (ref "U1") (pin "44") (pinfunction "PE13_44") (pintype "passive"))
    )
    (net (code "109") (name "Net-(U1C-PE14)") (class "Default")
      (node (ref "R46") (pin "2") (pintype "passive"))
      (node (ref "U1") (pin "45") (pinfunction "PE14_45") (pintype "passive"))
    )
    (net (code "110") (name "Net-(U1C-PE15)") (class "Default")
      (node (ref "R48") (pin "2") (pintype "passive"))
      (node (ref "U1") (pin "46") (pinfunction "PE15_46") (pintype "passive"))
    )
    (net (code "111") (name "Net-(X1-OSC2)") (class "Default")
      (node (ref "C17") (pin "2") (pinfunction "2_2") (pintype "passive"))
      (node (ref "R3") (pin "2") (pintype "passive"))
      (node (ref "X1") (pin "2") (pinfunction "OSC2_2") (pintype "passive"))
    )
    (net (code "112") (name "VDD_3V3") (class "Default")
      (node (ref "C1") (pin "1") (pinfunction "1_1") (pintype "passive"))
      (node (ref "C10") (pin "1") (pinfunction "1_1") (pintype "passive"))
      (node (ref "C11") (pin "1") (pinfunction "1_1") (pintype "passive"))
      (node (ref "C12") (pin "1") (pinfunction "1_1") (pintype "passive"))
      (node (ref "C2") (pin "1") (pinfunction "1_1") (pintype "passive"))
      (node (ref "C3") (pin "1") (pinfunction "1_1") (pintype "passive"))
      (node (ref "C4") (pin "1") (pinfunction "1_1") (pintype "passive"))
      (node (ref "C5") (pin "1") (pinfunction "1_1") (pintype "passive"))
      (node (ref "C6") (pin "1") (pinfunction "1_1") (pintype "passive"))
      (node (ref "C7") (pin "1") (pinfunction "1_1") (pintype "passive"))
      (node (ref "C8") (pin "1") (pinfunction "1_1") (pintype "passive"))
      (node (ref "C9") (pin "1") (pinfunction "1_1") (pintype "passive"))
      (node (ref "CF1") (pin "1") (pinfunction "1_1") (pintype "passive"))
      (node (ref "L1") (pin "1") (pinfunction "1_1") (pintype "passive"))
      (node (ref "R16") (pin "1") (pintype "passive"))
      (node (ref "RF4") (pin "1") (pintype "passive"))
      (node (ref "RF5") (pin "1") (pintype "passive"))
      (node (ref "U1") (pin "100") (pinfunction "VDD_100") (pintype "passive"))
      (node (ref "U1") (pin "11") (pinfunction "VDD_11") (pintype "passive"))
      (node (ref "U1") (pin "19") (pinfunction "VDD_19") (pintype "passive"))
      (node (ref "U1") (pin "28") (pinfunction "VDD_28") (pintype "passive"))
      (node (ref "U1") (pin "50") (pinfunction "VDD_50") (pintype "passive"))
      (node (ref "U1") (pin "6") (pinfunction "VBAT_6") (pintype "passive"))
      (node (ref "U1") (pin "75") (pinfunction "VDD_75") (pintype "passive"))
      (node (ref "U7") (pin "8") (pinfunction "VCC_8") (pintype "passive"))
    )
  )
)
